# espurna-h.net
KiCad netlist of a schematic drawn in EAGLE
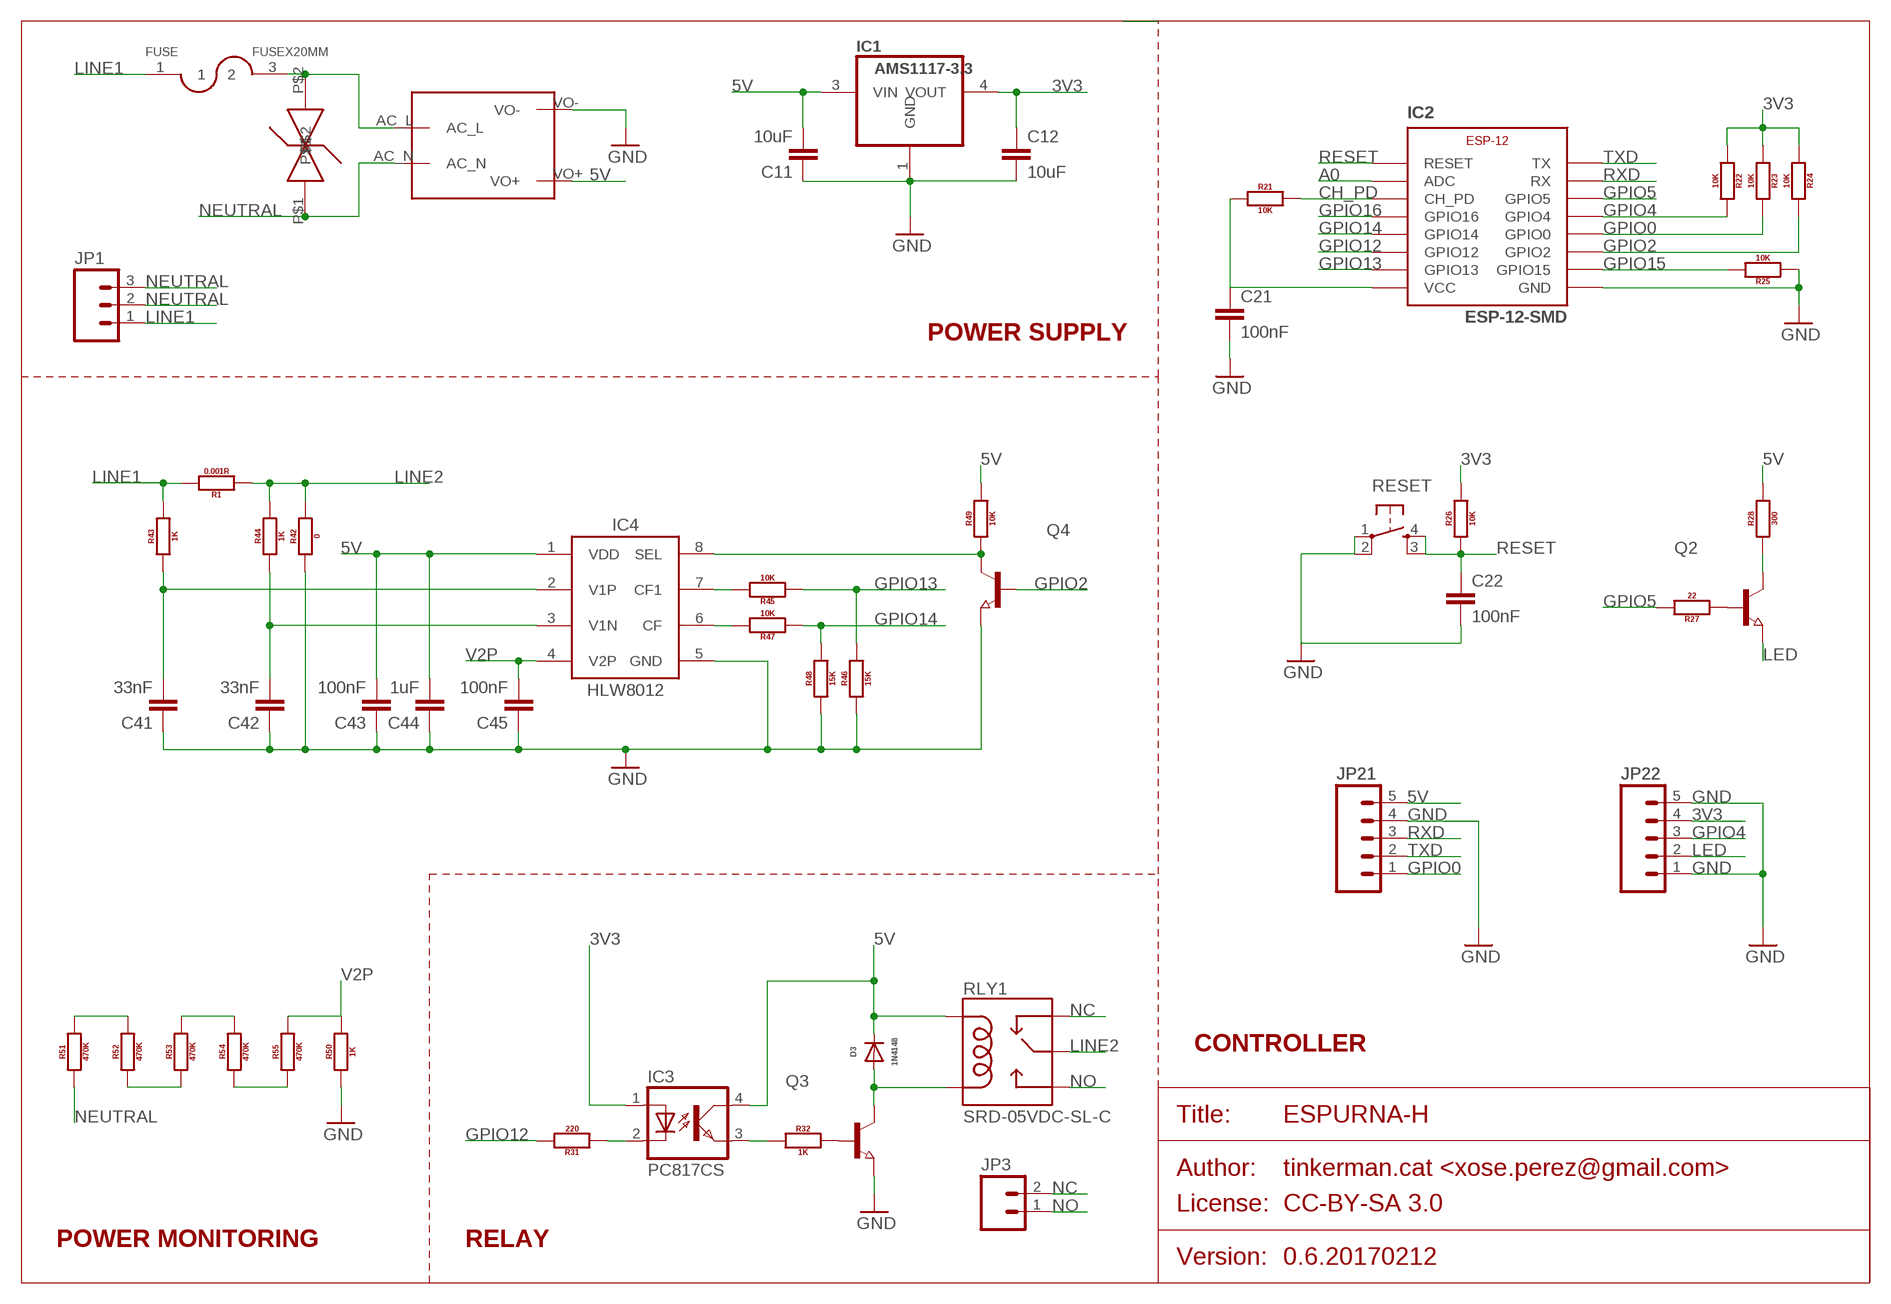
[diagram p0: schematic, sheet 1]

(export (version "E")
  (design (tool "Eeschema 10.0.6"))
  (components
    (comp (ref "C11")
      (value "10uF")
      (footprint "eagle-import:0805")
      (libsource (lib "eagle-import") (part "C-EU0805"))
    )
    (comp (ref "C12")
      (value "10uF")
      (footprint "eagle-import:0805")
      (libsource (lib "eagle-import") (part "C-EU0805"))
    )
    (comp (ref "C21")
      (value "100nF")
      (footprint "eagle-import:0805")
      (libsource (lib "eagle-import") (part "C-EU0805"))
    )
    (comp (ref "C22")
      (value "100nF")
      (footprint "eagle-import:0805")
      (libsource (lib "eagle-import") (part "C-EU0805"))
    )
    (comp (ref "C41")
      (value "33nF")
      (footprint "eagle-import:0805")
      (libsource (lib "eagle-import") (part "C-EU0805"))
    )
    (comp (ref "C42")
      (value "33nF")
      (footprint "eagle-import:0805")
      (libsource (lib "eagle-import") (part "C-EU0805"))
    )
    (comp (ref "C43")
      (value "100nF")
      (footprint "eagle-import:0805")
      (libsource (lib "eagle-import") (part "C-EU0805"))
    )
    (comp (ref "C44")
      (value "1uF")
      (footprint "eagle-import:0805")
      (libsource (lib "eagle-import") (part "C-EU0805"))
    )
    (comp (ref "C45")
      (value "100nF")
      (footprint "eagle-import:0805")
      (libsource (lib "eagle-import") (part "C-EU0805"))
    )
    (comp (ref "D3")
      (value "1N4148")
      (footprint "eagle-import:SOD80")
      (libsource (lib "eagle-import") (part "DIODE"))
    )
    (comp (ref "FUSE")
      (value "FUSEX20MM")
      (footprint "eagle-import:FUSE_5MM")
      (libsource (lib "eagle-import") (part "FUSEX20MM"))
    )
    (comp (ref "IC1")
      (value "AMS1117-3.3")
      (footprint "eagle-import:SOT223")
      (libsource (lib "eagle-import") (part "REG1117SOT223-2"))
    )
    (comp (ref "IC2")
      (value "ESP-12-SMD")
      (footprint "eagle-import:ESP-12-SMD")
      (libsource (lib "eagle-import") (part "ESP-12-SMD"))
    )
    (comp (ref "IC3")
      (value "PC817CS")
      (footprint "eagle-import:SMD4-7")
      (fields (field (name "MF") "VISHAY/TELEFUNKEN") (field (name "MPN") "SFH6186-2"))
      (libsource (lib "eagle-import") (part "SFH618?6-2"))
    )
    (comp (ref "IC4")
      (value "HLW8012")
      (footprint "eagle-import:SOP8")
      (libsource (lib "eagle-import") (part "HLW8012"))
    )
    (comp (ref "JP1")
      (value "M03200MIL")
      (footprint "eagle-import:SCREWTERMINAL-200MIL-3")
      (libsource (lib "eagle-import") (part "M03200MIL"))
    )
    (comp (ref "JP3")
      (value "M02200MIL")
      (footprint "eagle-import:SCREWTERMINAL-200MIL-2")
      (libsource (lib "eagle-import") (part "M02200MIL"))
    )
    (comp (ref "JP21")
      (value "M05PTH")
      (footprint "eagle-import:1X05")
      (libsource (lib "eagle-import") (part "M05PTH"))
    )
    (comp (ref "JP22")
      (value "M05PTH")
      (footprint "eagle-import:1X05")
      (libsource (lib "eagle-import") (part "M05PTH"))
    )
    (comp (ref "Q2")
      (value "NPN-TRANSISTOR_SOT23")
      (footprint "eagle-import:SOT23")
      (libsource (lib "eagle-import") (part "NPN-TRANSISTOR_SOT23"))
    )
    (comp (ref "Q3")
      (value "NPN-TRANSISTOR_SOT23")
      (footprint "eagle-import:SOT23")
      (libsource (lib "eagle-import") (part "NPN-TRANSISTOR_SOT23"))
    )
    (comp (ref "Q4")
      (value "NPN-TRANSISTOR_SOT23")
      (footprint "eagle-import:SOT23")
      (libsource (lib "eagle-import") (part "NPN-TRANSISTOR_SOT23"))
    )
    (comp (ref "R1")
      (value "0.001R")
      (footprint "eagle-import:2512")
      (libsource (lib "eagle-import") (part "RESISTOR2512"))
    )
    (comp (ref "R21")
      (value "10K")
      (footprint "eagle-import:0805")
      (libsource (lib "eagle-import") (part "RESISTOR0805"))
    )
    (comp (ref "R22")
      (value "10K")
      (footprint "eagle-import:0805")
      (libsource (lib "eagle-import") (part "RESISTOR0805"))
    )
    (comp (ref "R23")
      (value "10K")
      (footprint "eagle-import:0805")
      (libsource (lib "eagle-import") (part "RESISTOR0805"))
    )
    (comp (ref "R24")
      (value "10K")
      (footprint "eagle-import:0805")
      (libsource (lib "eagle-import") (part "RESISTOR0805"))
    )
    (comp (ref "R25")
      (value "10K")
      (footprint "eagle-import:0805")
      (libsource (lib "eagle-import") (part "RESISTOR0805"))
    )
    (comp (ref "R26")
      (value "10K")
      (footprint "eagle-import:0805")
      (libsource (lib "eagle-import") (part "RESISTOR0805"))
    )
    (comp (ref "R27")
      (value "22")
      (footprint "eagle-import:0805")
      (libsource (lib "eagle-import") (part "RESISTOR0805"))
    )
    (comp (ref "R28")
      (value "300")
      (footprint "eagle-import:0805")
      (libsource (lib "eagle-import") (part "RESISTOR0805"))
    )
    (comp (ref "R31")
      (value "220")
      (footprint "eagle-import:0805")
      (libsource (lib "eagle-import") (part "RESISTOR0805"))
    )
    (comp (ref "R32")
      (value "1K")
      (footprint "eagle-import:0805")
      (libsource (lib "eagle-import") (part "RESISTOR0805"))
    )
    (comp (ref "R42")
      (value "0")
      (footprint "eagle-import:1206")
      (libsource (lib "eagle-import") (part "RESISTOR1206"))
    )
    (comp (ref "R43")
      (value "1K")
      (footprint "eagle-import:0805")
      (libsource (lib "eagle-import") (part "RESISTOR0805"))
    )
    (comp (ref "R44")
      (value "1K")
      (footprint "eagle-import:0805")
      (libsource (lib "eagle-import") (part "RESISTOR0805"))
    )
    (comp (ref "R45")
      (value "10K")
      (footprint "eagle-import:0805")
      (libsource (lib "eagle-import") (part "RESISTOR0805"))
    )
    (comp (ref "R46")
      (value "15K")
      (footprint "eagle-import:0805")
      (libsource (lib "eagle-import") (part "RESISTOR0805"))
    )
    (comp (ref "R47")
      (value "10K")
      (footprint "eagle-import:0805")
      (libsource (lib "eagle-import") (part "RESISTOR0805"))
    )
    (comp (ref "R48")
      (value "15K")
      (footprint "eagle-import:0805")
      (libsource (lib "eagle-import") (part "RESISTOR0805"))
    )
    (comp (ref "R49")
      (value "10K")
      (footprint "eagle-import:0805")
      (libsource (lib "eagle-import") (part "RESISTOR0805"))
    )
    (comp (ref "R50")
      (value "1K")
      (footprint "eagle-import:0805")
      (libsource (lib "eagle-import") (part "RESISTOR0805"))
    )
    (comp (ref "R51")
      (value "470K")
      (footprint "eagle-import:0805")
      (libsource (lib "eagle-import") (part "RESISTOR0805"))
    )
    (comp (ref "R52")
      (value "470K")
      (footprint "eagle-import:0805")
      (libsource (lib "eagle-import") (part "RESISTOR0805"))
    )
    (comp (ref "R53")
      (value "470K")
      (footprint "eagle-import:0805")
      (libsource (lib "eagle-import") (part "RESISTOR0805"))
    )
    (comp (ref "R54")
      (value "470K")
      (footprint "eagle-import:0805")
      (libsource (lib "eagle-import") (part "RESISTOR0805"))
    )
    (comp (ref "R55")
      (value "470K")
      (footprint "eagle-import:0805")
      (libsource (lib "eagle-import") (part "RESISTOR0805"))
    )
    (comp (ref "RESET")
      (value "TACTILE_BUTTON_SMD")
      (footprint "eagle-import:TACTILE-BUTTON-SMD")
      (libsource (lib "eagle-import") (part "TACTILE_BUTTON_SMD"))
    )
    (comp (ref "RLY1")
      (value "SRD-05VDC-SL-C")
      (footprint "eagle-import:SRD-5VDC-SL-C")
      (libsource (lib "eagle-import") (part "RELAYSONGLE"))
    )
    (comp (ref "U$1")
      (value "MAINS_CONVERTERS")
      (footprint "eagle-import:HLK-PM01")
      (libsource (lib "eagle-import") (part "MAINS_CONVERTERS"))
    )
    (comp (ref "VARISTOR")
      (value "V18ZA2P")
      (footprint "eagle-import:V18ZA2P")
      (libsource (lib "eagle-import") (part "V18ZA2P"))
    )
  )
  (nets
    (net (code "1") (name "/3V3") (class "Default")
      (node (ref "C12") (pin "1") (pinfunction "1_1") (pintype "passive"))
      (node (ref "C21") (pin "1") (pinfunction "1_1") (pintype "passive"))
      (node (ref "IC1") (pin "4") (pinfunction "VOUT_4") (pintype "output"))
      (node (ref "IC2") (pin "VCC") (pinfunction "VCC_VCC") (pintype "bidirectional"))
      (node (ref "IC3") (pin "1") (pinfunction "A_1") (pintype "passive"))
      (node (ref "JP22") (pin "4") (pinfunction "4_4") (pintype "passive"))
      (node (ref "R21") (pin "1") (pinfunction "1_1") (pintype "passive"))
      (node (ref "R22") (pin "1") (pinfunction "1_1") (pintype "passive"))
      (node (ref "R23") (pin "1") (pinfunction "1_1") (pintype "passive"))
      (node (ref "R24") (pin "1") (pinfunction "1_1") (pintype "passive"))
      (node (ref "R26") (pin "2") (pinfunction "2_2") (pintype "passive"))
    )
    (net (code "2") (name "/5V") (class "Default")
      (node (ref "C11") (pin "2") (pinfunction "2_2") (pintype "passive"))
      (node (ref "C43") (pin "2") (pinfunction "2_2") (pintype "passive"))
      (node (ref "C44") (pin "2") (pinfunction "2_2") (pintype "passive"))
      (node (ref "D3") (pin "2") (pinfunction "C_2") (pintype "passive"))
      (node (ref "IC1") (pin "3") (pinfunction "VIN_3") (pintype "input"))
      (node (ref "IC3") (pin "4") (pinfunction "COL_4") (pintype "passive"))
      (node (ref "IC4") (pin "1") (pinfunction "VDD_1") (pintype "power_in"))
      (node (ref "JP21") (pin "5") (pinfunction "5_5") (pintype "passive"))
      (node (ref "R28") (pin "2") (pinfunction "2_2") (pintype "passive"))
      (node (ref "R49") (pin "2") (pinfunction "2_2") (pintype "passive"))
      (node (ref "RLY1") (pin "COIL1") (pinfunction "COIL1_COIL1") (pintype "bidirectional"))
      (node (ref "U$1") (pin "VO+") (pinfunction "VO+_VO+") (pintype "output"))
    )
    (net (code "3") (name "/A0") (class "Default")
      (node (ref "IC2") (pin "ADC") (pinfunction "ADC_ADC") (pintype "bidirectional"))
    )
    (net (code "4") (name "/CH_PD") (class "Default")
      (node (ref "IC2") (pin "CH_PD") (pinfunction "CH_PD_CH_PD") (pintype "bidirectional"))
      (node (ref "R21") (pin "2") (pinfunction "2_2") (pintype "passive"))
    )
    (net (code "5") (name "/GPIO0") (class "Default")
      (node (ref "IC2") (pin "GPIO0") (pinfunction "GPIO0_GPIO0") (pintype "bidirectional"))
      (node (ref "JP21") (pin "1") (pinfunction "1_1") (pintype "passive"))
      (node (ref "R23") (pin "2") (pinfunction "2_2") (pintype "passive"))
    )
    (net (code "6") (name "/GPIO2") (class "Default")
      (node (ref "IC2") (pin "GPIO2") (pinfunction "GPIO2_GPIO2") (pintype "bidirectional"))
      (node (ref "Q4") (pin "1") (pinfunction "B_1") (pintype "passive"))
      (node (ref "R24") (pin "2") (pinfunction "2_2") (pintype "passive"))
    )
    (net (code "7") (name "/GPIO4") (class "Default")
      (node (ref "IC2") (pin "GPIO4") (pinfunction "GPIO4_GPIO4") (pintype "bidirectional"))
      (node (ref "JP22") (pin "3") (pinfunction "3_3") (pintype "passive"))
      (node (ref "R22") (pin "2") (pinfunction "2_2") (pintype "passive"))
    )
    (net (code "8") (name "/GPIO5") (class "Default")
      (node (ref "IC2") (pin "GPIO5") (pinfunction "GPIO5_GPIO5") (pintype "bidirectional"))
      (node (ref "R27") (pin "2") (pinfunction "2_2") (pintype "passive"))
    )
    (net (code "9") (name "/GPIO12") (class "Default")
      (node (ref "IC2") (pin "GPIO12") (pinfunction "GPIO12_GPIO12") (pintype "bidirectional"))
      (node (ref "R31") (pin "2") (pinfunction "2_2") (pintype "passive"))
    )
    (net (code "10") (name "/GPIO13") (class "Default")
      (node (ref "IC2") (pin "GPIO13") (pinfunction "GPIO13_GPIO13") (pintype "bidirectional"))
      (node (ref "R45") (pin "1") (pinfunction "1_1") (pintype "passive"))
      (node (ref "R46") (pin "2") (pinfunction "2_2") (pintype "passive"))
    )
    (net (code "11") (name "/GPIO14") (class "Default")
      (node (ref "IC2") (pin "GPIO14") (pinfunction "GPIO14_GPIO14") (pintype "bidirectional"))
      (node (ref "R47") (pin "1") (pinfunction "1_1") (pintype "passive"))
      (node (ref "R48") (pin "2") (pinfunction "2_2") (pintype "passive"))
    )
    (net (code "12") (name "/GPIO15") (class "Default")
      (node (ref "IC2") (pin "GPIO15") (pinfunction "GPIO15_GPIO15") (pintype "bidirectional"))
      (node (ref "R25") (pin "2") (pinfunction "2_2") (pintype "passive"))
    )
    (net (code "13") (name "/GPIO16") (class "Default")
      (node (ref "IC2") (pin "GPIO16") (pinfunction "GPIO16_GPIO16") (pintype "bidirectional"))
    )
    (net (code "14") (name "/LED") (class "Default")
      (node (ref "JP22") (pin "2") (pinfunction "2_2") (pintype "passive"))
      (node (ref "Q2") (pin "2") (pinfunction "E_2") (pintype "passive"))
    )
    (net (code "15") (name "/LINE1") (class "Default")
      (node (ref "FUSE") (pin "1") (pinfunction "1_1") (pintype "bidirectional"))
      (node (ref "JP1") (pin "1") (pinfunction "1_1") (pintype "passive"))
      (node (ref "R1") (pin "2") (pinfunction "2_2") (pintype "passive"))
      (node (ref "R43") (pin "2") (pinfunction "2_2") (pintype "passive"))
    )
    (net (code "16") (name "/LINE2") (class "Default")
      (node (ref "R1") (pin "1") (pinfunction "1_1") (pintype "passive"))
      (node (ref "R42") (pin "2") (pinfunction "2_2") (pintype "passive"))
      (node (ref "R44") (pin "2") (pinfunction "2_2") (pintype "passive"))
      (node (ref "RLY1") (pin "COMMON") (pinfunction "MAIN_COMMON") (pintype "bidirectional"))
    )
    (net (code "17") (name "/NC") (class "Default")
      (node (ref "JP3") (pin "2") (pinfunction "2_2") (pintype "passive"))
      (node (ref "RLY1") (pin "CLOSED") (pinfunction "NC_CLOSED") (pintype "bidirectional"))
    )
    (net (code "18") (name "/NEUTRAL") (class "Default")
      (node (ref "JP1") (pin "2") (pinfunction "2_2") (pintype "passive"))
      (node (ref "JP1") (pin "3") (pinfunction "3_3") (pintype "passive"))
      (node (ref "R51") (pin "1") (pinfunction "1_1") (pintype "passive"))
      (node (ref "U$1") (pin "AC_N") (pinfunction "AC_N_AC_N") (pintype "input"))
      (node (ref "VARISTOR") (pin "P$1") (pinfunction "P$1_P$1") (pintype "bidirectional"))
    )
    (net (code "19") (name "/NO") (class "Default")
      (node (ref "JP3") (pin "1") (pinfunction "1_1") (pintype "passive"))
      (node (ref "RLY1") (pin "OPEN") (pinfunction "NO_OPEN") (pintype "bidirectional"))
    )
    (net (code "20") (name "/RESET") (class "Default")
      (node (ref "C22") (pin "1") (pinfunction "1_1") (pintype "passive"))
      (node (ref "IC2") (pin "RESET") (pinfunction "RESET_RESET") (pintype "bidirectional"))
      (node (ref "R26") (pin "1") (pinfunction "1_1") (pintype "passive"))
      (node (ref "RESET") (pin "3") (pinfunction "SWB2_3") (pintype "passive"))
      (node (ref "RESET") (pin "4") (pinfunction "SWA2_4") (pintype "passive"))
    )
    (net (code "21") (name "/RXD") (class "Default")
      (node (ref "IC2") (pin "RX") (pinfunction "RX_RX") (pintype "bidirectional"))
      (node (ref "JP21") (pin "3") (pinfunction "3_3") (pintype "passive"))
    )
    (net (code "22") (name "/TXD") (class "Default")
      (node (ref "IC2") (pin "TX") (pinfunction "TX_TX") (pintype "bidirectional"))
      (node (ref "JP21") (pin "2") (pinfunction "2_2") (pintype "passive"))
    )
    (net (code "23") (name "/V2P") (class "Default")
      (node (ref "C45") (pin "2") (pinfunction "2_2") (pintype "passive"))
      (node (ref "IC4") (pin "4") (pinfunction "V2P_4") (pintype "input"))
      (node (ref "R50") (pin "2") (pinfunction "2_2") (pintype "passive"))
      (node (ref "R55") (pin "2") (pinfunction "2_2") (pintype "passive"))
    )
    (net (code "24") (name "GND") (class "Default")
      (node (ref "C11") (pin "1") (pinfunction "1_1") (pintype "passive"))
      (node (ref "C12") (pin "2") (pinfunction "2_2") (pintype "passive"))
      (node (ref "C21") (pin "2") (pinfunction "2_2") (pintype "passive"))
      (node (ref "C22") (pin "2") (pinfunction "2_2") (pintype "passive"))
      (node (ref "C41") (pin "1") (pinfunction "1_1") (pintype "passive"))
      (node (ref "C42") (pin "1") (pinfunction "1_1") (pintype "passive"))
      (node (ref "C43") (pin "1") (pinfunction "1_1") (pintype "passive"))
      (node (ref "C44") (pin "1") (pinfunction "1_1") (pintype "passive"))
      (node (ref "C45") (pin "1") (pinfunction "1_1") (pintype "passive"))
      (node (ref "IC1") (pin "1") (pinfunction "GND_1") (pintype "power_in"))
      (node (ref "IC2") (pin "GND") (pinfunction "GND_GND") (pintype "bidirectional"))
      (node (ref "IC4") (pin "5") (pinfunction "GND_5") (pintype "power_in"))
      (node (ref "JP21") (pin "4") (pinfunction "4_4") (pintype "passive"))
      (node (ref "JP22") (pin "1") (pinfunction "1_1") (pintype "passive"))
      (node (ref "JP22") (pin "5") (pinfunction "5_5") (pintype "passive"))
      (node (ref "Q3") (pin "2") (pinfunction "E_2") (pintype "passive"))
      (node (ref "Q4") (pin "2") (pinfunction "E_2") (pintype "passive"))
      (node (ref "R25") (pin "1") (pinfunction "1_1") (pintype "passive"))
      (node (ref "R42") (pin "1") (pinfunction "1_1") (pintype "passive"))
      (node (ref "R46") (pin "1") (pinfunction "1_1") (pintype "passive"))
      (node (ref "R48") (pin "1") (pinfunction "1_1") (pintype "passive"))
      (node (ref "R50") (pin "1") (pinfunction "1_1") (pintype "passive"))
      (node (ref "RESET") (pin "1") (pinfunction "SWA1_1") (pintype "passive"))
      (node (ref "RESET") (pin "2") (pinfunction "SWB1_2") (pintype "passive"))
      (node (ref "U$1") (pin "VO-") (pinfunction "VO-_VO-") (pintype "output"))
    )
    (net (code "25") (name "Net-(D3-A)") (class "Default")
      (node (ref "D3") (pin "1") (pinfunction "A_1") (pintype "passive"))
      (node (ref "Q3") (pin "3") (pinfunction "C_3") (pintype "passive"))
      (node (ref "RLY1") (pin "COIL2") (pinfunction "COIL2_COIL2") (pintype "bidirectional"))
    )
    (net (code "26") (name "Net-(FUSE-2)") (class "Default")
      (node (ref "FUSE") (pin "3") (pinfunction "2_3") (pintype "bidirectional"))
      (node (ref "U$1") (pin "AC_L") (pinfunction "AC_L_AC_L") (pintype "input"))
      (node (ref "VARISTOR") (pin "P$2") (pinfunction "P$2_P$2") (pintype "bidirectional"))
    )
    (net (code "27") (name "Net-(IC3-C)") (class "Default")
      (node (ref "IC3") (pin "2") (pinfunction "C_2") (pintype "passive"))
      (node (ref "R31") (pin "1") (pinfunction "1_1") (pintype "passive"))
    )
    (net (code "28") (name "Net-(IC3-EMIT)") (class "Default")
      (node (ref "IC3") (pin "3") (pinfunction "EMIT_3") (pintype "passive"))
      (node (ref "R32") (pin "1") (pinfunction "1_1") (pintype "passive"))
    )
    (net (code "29") (name "Net-(IC4-CF)") (class "Default")
      (node (ref "IC4") (pin "6") (pinfunction "CF_6") (pintype "output"))
      (node (ref "R47") (pin "2") (pinfunction "2_2") (pintype "passive"))
    )
    (net (code "30") (name "Net-(IC4-CF1)") (class "Default")
      (node (ref "IC4") (pin "7") (pinfunction "CF1_7") (pintype "output"))
      (node (ref "R45") (pin "2") (pinfunction "2_2") (pintype "passive"))
    )
    (net (code "31") (name "Net-(IC4-SEL)") (class "Default")
      (node (ref "IC4") (pin "8") (pinfunction "SEL_8") (pintype "input"))
      (node (ref "Q4") (pin "3") (pinfunction "C_3") (pintype "passive"))
      (node (ref "R49") (pin "1") (pinfunction "1_1") (pintype "passive"))
    )
    (net (code "32") (name "Net-(IC4-V1N)") (class "Default")
      (node (ref "C42") (pin "2") (pinfunction "2_2") (pintype "passive"))
      (node (ref "IC4") (pin "3") (pinfunction "V1N_3") (pintype "input"))
      (node (ref "R44") (pin "1") (pinfunction "1_1") (pintype "passive"))
    )
    (net (code "33") (name "Net-(IC4-V1P)") (class "Default")
      (node (ref "C41") (pin "2") (pinfunction "2_2") (pintype "passive"))
      (node (ref "IC4") (pin "2") (pinfunction "V1P_2") (pintype "input"))
      (node (ref "R43") (pin "1") (pinfunction "1_1") (pintype "passive"))
    )
    (net (code "34") (name "Net-(Q2-B)") (class "Default")
      (node (ref "Q2") (pin "1") (pinfunction "B_1") (pintype "passive"))
      (node (ref "R27") (pin "1") (pinfunction "1_1") (pintype "passive"))
    )
    (net (code "35") (name "Net-(Q2-C)") (class "Default")
      (node (ref "Q2") (pin "3") (pinfunction "C_3") (pintype "passive"))
      (node (ref "R28") (pin "1") (pinfunction "1_1") (pintype "passive"))
    )
    (net (code "36") (name "Net-(Q3-B)") (class "Default")
      (node (ref "Q3") (pin "1") (pinfunction "B_1") (pintype "passive"))
      (node (ref "R32") (pin "2") (pinfunction "2_2") (pintype "passive"))
    )
    (net (code "37") (name "Net-(R51-Pad2)") (class "Default")
      (node (ref "R51") (pin "2") (pinfunction "2_2") (pintype "passive"))
      (node (ref "R52") (pin "2") (pinfunction "2_2") (pintype "passive"))
    )
    (net (code "38") (name "Net-(R52-Pad1)") (class "Default")
      (node (ref "R52") (pin "1") (pinfunction "1_1") (pintype "passive"))
      (node (ref "R53") (pin "1") (pinfunction "1_1") (pintype "passive"))
    )
    (net (code "39") (name "Net-(R53-Pad2)") (class "Default")
      (node (ref "R53") (pin "2") (pinfunction "2_2") (pintype "passive"))
      (node (ref "R54") (pin "2") (pinfunction "2_2") (pintype "passive"))
    )
    (net (code "40") (name "Net-(R54-Pad1)") (class "Default")
      (node (ref "R54") (pin "1") (pinfunction "1_1") (pintype "passive"))
      (node (ref "R55") (pin "1") (pinfunction "1_1") (pintype "passive"))
    )
  )
)
